# Laser_Array_Charging_board.net
KiCad netlist of a schematic drawn in EAGLE
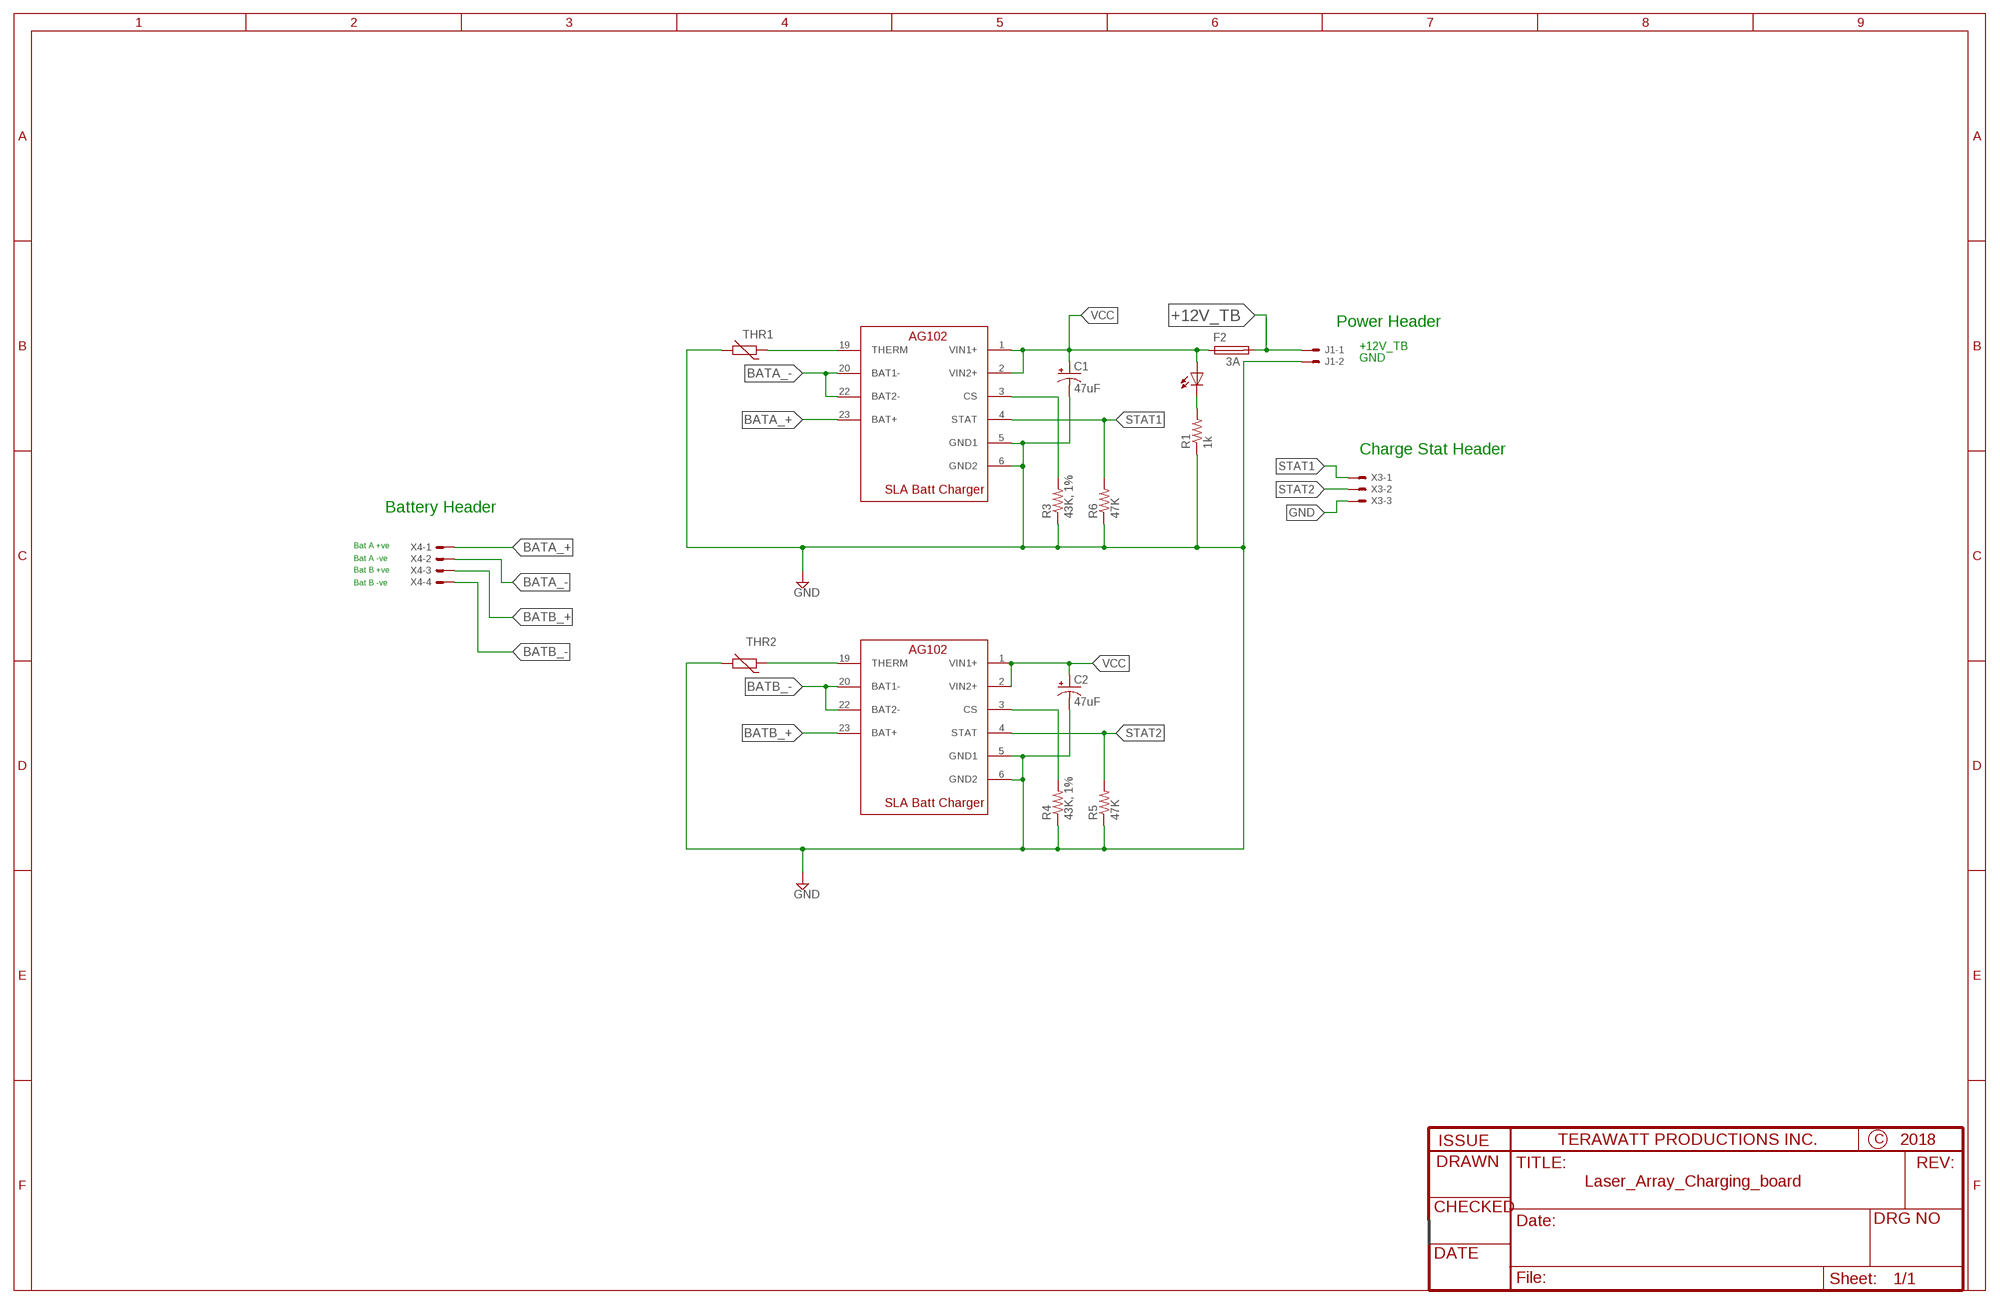
[diagram p0: schematic, sheet 1]

(export (version "E")
  (design (tool "Eeschema 10.0.6"))
  (components
    (comp (ref "C1")
      (value "47uF")
      (footprint "eagle-import:E5-10,5")
      (libsource (lib "eagle-import") (part "CPOL-USE5-10.5"))
    )
    (comp (ref "C2")
      (value "47uF")
      (footprint "eagle-import:E5-10,5")
      (libsource (lib "eagle-import") (part "CPOL-USE5-10.5"))
    )
    (comp (ref "CHG1")
      (value "AG102_SLA_CHARGER")
      (footprint "eagle-import:SLA_CHARGER")
      (libsource (lib "eagle-import") (part "AG102_SLA_CHARGER"))
    )
    (comp (ref "CHG2")
      (value "AG102_SLA_CHARGER")
      (footprint "eagle-import:SLA_CHARGER")
      (libsource (lib "eagle-import") (part "AG102_SLA_CHARGER"))
    )
    (comp (ref "F2")
      (value "3A")
      (footprint "eagle-import:SH22,5")
      (fields (field (name "MF") "SCHURTER") (field (name "MPN") "0031.8201"))
      (libsource (lib "eagle-import") (part "SH22,5"))
    )
    (comp (ref "J1")
      (value "22-23-2021")
      (footprint "eagle-import:22-23-2021")
      (fields (field (name "MF") "MOLEX"))
      (libsource (lib "eagle-import") (part "22-23-2021"))
    )
    (comp (ref "LED1")
      (value "LEDCHIPLED_0805")
      (footprint "eagle-import:CHIPLED_0805")
      (libsource (lib "eagle-import") (part "LEDCHIPLED_0805"))
    )
    (comp (ref "R1")
      (value "1k")
      (footprint "eagle-import:M0805")
      (libsource (lib "eagle-import") (part "R-US_M0805"))
    )
    (comp (ref "R3")
      (value "43K, 1%")
      (footprint "eagle-import:R0805")
      (libsource (lib "eagle-import") (part "R-US_R0805"))
    )
    (comp (ref "R4")
      (value "43K, 1%")
      (footprint "eagle-import:R0805")
      (libsource (lib "eagle-import") (part "R-US_R0805"))
    )
    (comp (ref "R5")
      (value "47K")
      (footprint "eagle-import:R0805")
      (libsource (lib "eagle-import") (part "R-US_R0805"))
    )
    (comp (ref "R6")
      (value "47K")
      (footprint "eagle-import:R0805")
      (libsource (lib "eagle-import") (part "R-US_R0805"))
    )
    (comp (ref "THR1")
      (value "THERMISTOR-2,5")
      (footprint "eagle-import:RS-2,5")
      (libsource (lib "eagle-import") (part "THERMISTOR-2,5"))
    )
    (comp (ref "THR2")
      (value "THERMISTOR-2,5")
      (footprint "eagle-import:RS-2,5")
      (libsource (lib "eagle-import") (part "THERMISTOR-2,5"))
    )
    (comp (ref "X3")
      (value "22-23-2031")
      (footprint "eagle-import:22-23-2031")
      (fields (field (name "MF") "MOLEX"))
      (libsource (lib "eagle-import") (part "22-23-2031"))
    )
    (comp (ref "X4")
      (value "22-23-2041")
      (footprint "eagle-import:22-23-2041")
      (fields (field (name "MF") "MOLEX"))
      (libsource (lib "eagle-import") (part "22-23-2041"))
    )
  )
  (nets
    (net (code "1") (name "+12V_TB") (class "Default")
      (node (ref "F2") (pin "2") (pinfunction "2_2") (pintype "passive"))
      (node (ref "J1") (pin "1") (pinfunction "S_1") (pintype "passive"))
    )
    (net (code "2") (name "BATA_+") (class "Default")
      (node (ref "CHG1") (pin "23") (pinfunction "BAT+_23") (pintype "bidirectional"))
      (node (ref "X4") (pin "1") (pinfunction "S_1") (pintype "passive"))
    )
    (net (code "3") (name "BATA_-") (class "Default")
      (node (ref "CHG1") (pin "20") (pinfunction "BAT1-_20") (pintype "bidirectional"))
      (node (ref "CHG1") (pin "22") (pinfunction "BAT2-_22") (pintype "bidirectional"))
      (node (ref "X4") (pin "2") (pinfunction "S_2") (pintype "passive"))
    )
    (net (code "4") (name "BATB_+") (class "Default")
      (node (ref "CHG2") (pin "23") (pinfunction "BAT+_23") (pintype "bidirectional"))
      (node (ref "X4") (pin "3") (pinfunction "S_3") (pintype "passive"))
    )
    (net (code "5") (name "BATB_-") (class "Default")
      (node (ref "CHG2") (pin "20") (pinfunction "BAT1-_20") (pintype "bidirectional"))
      (node (ref "CHG2") (pin "22") (pinfunction "BAT2-_22") (pintype "bidirectional"))
      (node (ref "X4") (pin "4") (pinfunction "S_4") (pintype "passive"))
    )
    (net (code "6") (name "GND") (class "Default")
      (node (ref "C1") (pin "-") (pinfunction "-_-") (pintype "passive"))
      (node (ref "C2") (pin "-") (pinfunction "-_-") (pintype "passive"))
      (node (ref "CHG1") (pin "5") (pinfunction "GND1_5") (pintype "bidirectional"))
      (node (ref "CHG1") (pin "6") (pinfunction "GND2_6") (pintype "bidirectional"))
      (node (ref "CHG2") (pin "5") (pinfunction "GND1_5") (pintype "bidirectional"))
      (node (ref "CHG2") (pin "6") (pinfunction "GND2_6") (pintype "bidirectional"))
      (node (ref "J1") (pin "2") (pinfunction "S_2") (pintype "passive"))
      (node (ref "R1") (pin "1") (pinfunction "1_1") (pintype "passive"))
      (node (ref "R3") (pin "1") (pinfunction "1_1") (pintype "passive"))
      (node (ref "R4") (pin "1") (pinfunction "1_1") (pintype "passive"))
      (node (ref "R5") (pin "1") (pinfunction "1_1") (pintype "passive"))
      (node (ref "R6") (pin "1") (pinfunction "1_1") (pintype "passive"))
      (node (ref "THR1") (pin "2") (pinfunction "2_2") (pintype "passive"))
      (node (ref "THR2") (pin "2") (pinfunction "2_2") (pintype "passive"))
      (node (ref "X3") (pin "3") (pinfunction "S_3") (pintype "passive"))
    )
    (net (code "7") (name "Net-(CHG1-CS)") (class "Default")
      (node (ref "CHG1") (pin "3") (pinfunction "CS_3") (pintype "bidirectional"))
      (node (ref "R3") (pin "2") (pinfunction "2_2") (pintype "passive"))
    )
    (net (code "8") (name "Net-(CHG1-THERM)") (class "Default")
      (node (ref "CHG1") (pin "19") (pinfunction "THERM_19") (pintype "bidirectional"))
      (node (ref "THR1") (pin "1") (pinfunction "1_1") (pintype "passive"))
    )
    (net (code "9") (name "Net-(CHG2-CS)") (class "Default")
      (node (ref "CHG2") (pin "3") (pinfunction "CS_3") (pintype "bidirectional"))
      (node (ref "R4") (pin "2") (pinfunction "2_2") (pintype "passive"))
    )
    (net (code "10") (name "Net-(CHG2-THERM)") (class "Default")
      (node (ref "CHG2") (pin "19") (pinfunction "THERM_19") (pintype "bidirectional"))
      (node (ref "THR2") (pin "1") (pinfunction "1_1") (pintype "passive"))
    )
    (net (code "11") (name "Net-(LED1-PadC)") (class "Default")
      (node (ref "LED1") (pin "C") (pinfunction "C_C") (pintype "passive"))
      (node (ref "R1") (pin "2") (pinfunction "2_2") (pintype "passive"))
    )
    (net (code "12") (name "STAT1") (class "Default")
      (node (ref "CHG1") (pin "4") (pinfunction "STAT_4") (pintype "bidirectional"))
      (node (ref "R6") (pin "2") (pinfunction "2_2") (pintype "passive"))
      (node (ref "X3") (pin "1") (pinfunction "S_1") (pintype "passive"))
    )
    (net (code "13") (name "STAT2") (class "Default")
      (node (ref "CHG2") (pin "4") (pinfunction "STAT_4") (pintype "bidirectional"))
      (node (ref "R5") (pin "2") (pinfunction "2_2") (pintype "passive"))
      (node (ref "X3") (pin "2") (pinfunction "S_2") (pintype "passive"))
    )
    (net (code "14") (name "VCC") (class "Default")
      (node (ref "C1") (pin "+") (pinfunction "+_+") (pintype "passive"))
      (node (ref "C2") (pin "+") (pinfunction "+_+") (pintype "passive"))
      (node (ref "CHG1") (pin "1") (pinfunction "VIN1+_1") (pintype "bidirectional"))
      (node (ref "CHG1") (pin "2") (pinfunction "VIN2+_2") (pintype "bidirectional"))
      (node (ref "CHG2") (pin "1") (pinfunction "VIN1+_1") (pintype "bidirectional"))
      (node (ref "CHG2") (pin "2") (pinfunction "VIN2+_2") (pintype "bidirectional"))
      (node (ref "F2") (pin "1") (pinfunction "1_1") (pintype "passive"))
      (node (ref "LED1") (pin "A") (pinfunction "A_A") (pintype "passive"))
    )
  )
)
